# Power.net
KiCad netlist of a schematic drawn in Altium Designer
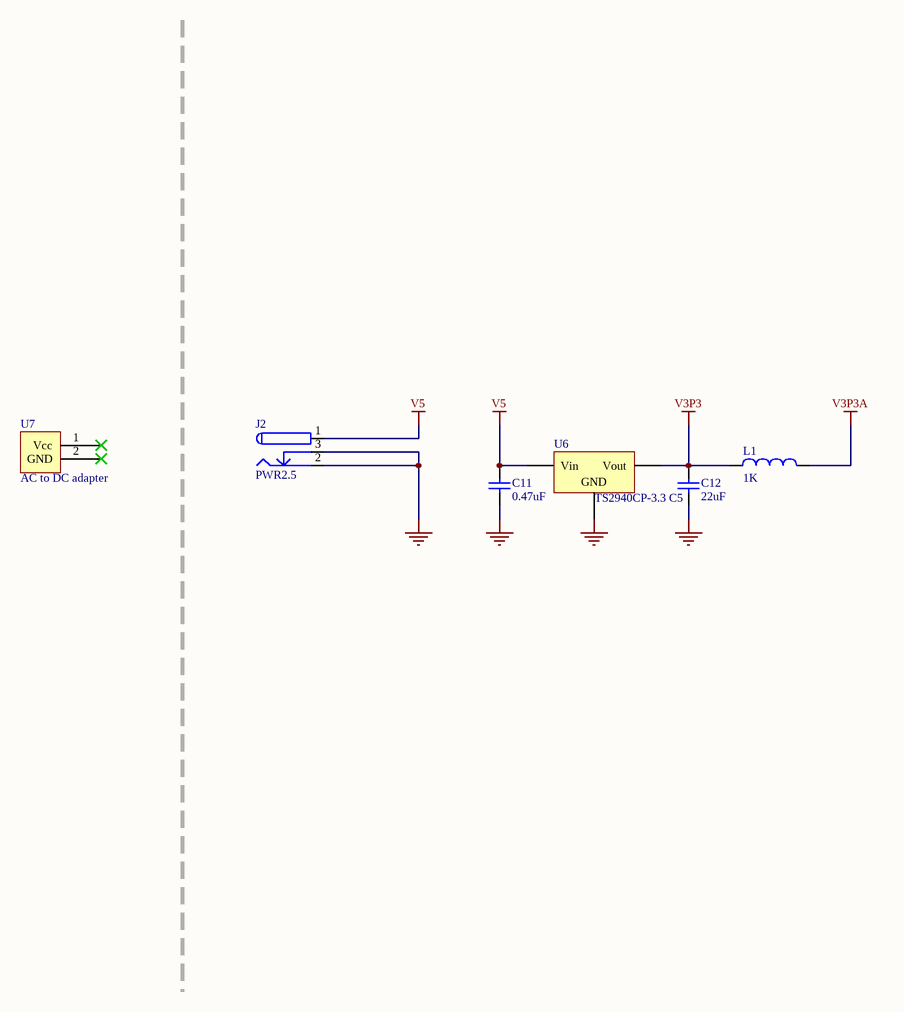
[diagram p0: Power.SchDoc]

(export (version "E")
  (design (tool "Eeschema 10.0.6"))
  (components
    (comp (ref "C11")
      (value "0.47uF")
      (footprint "CAP0603")
      (description "Capacitor")
      (fields (field (name "PUBLISHER") "Altium Limited"))
      (libsource (lib "Miscellaneous Devices") (part "Cap"))
    )
    (comp (ref "C12")
      (value "22uF")
      (footprint "CAP0603")
      (description "Capacitor")
      (fields (field (name "PUBLISHER") "Altium Limited"))
      (libsource (lib "Miscellaneous Devices") (part "Cap"))
    )
    (comp (ref "J2")
      (value "PWR2.5")
      (footprint "MJ-179PH")
      (description "Low Voltage Power Supply Connector")
      (libsource (lib "Miscellaneous Connectors") (part "PWR2.5"))
    )
    (comp (ref "L1")
      (value "1K")
      (footprint "IND0603")
      (description "Inductor")
      (fields (field (name "PUBLISHER") "Altium Limited"))
      (libsource (lib "Miscellaneous Devices") (part "Inductor"))
    )
    (comp (ref "U6")
      (value "TS2940CP-3.3 C5")
      (footprint "TS2940CP-3.3 C5")
      (description "Voltage Regulator")
      (libsource (lib "Miscellaneous Devices") (part "Volt Reg"))
    )
    (comp (ref "U7")
      (value "AC to DC adapter")
      (description "Power adapter")
      (libsource (lib "Components") (part "25HK-AB-050A400-CP"))
    )
  )
  (nets
    (net (code "1") (name "GND") (class "Default")
      (node (ref "C11") (pin "1") (pinfunction "1_1") (pintype "passive"))
      (node (ref "C12") (pin "1") (pinfunction "1_1") (pintype "passive"))
      (node (ref "J2") (pin "2") (pinfunction "2_2") (pintype "power_in"))
      (node (ref "J2") (pin "3") (pinfunction "3_3") (pintype "power_in"))
      (node (ref "U6") (pin "2") (pinfunction "GND_2") (pintype "passive"))
    )
    (net (code "2") (name "V3P3") (class "Default")
      (node (ref "C12") (pin "2") (pinfunction "2_2") (pintype "passive"))
      (node (ref "L1") (pin "1") (pinfunction "1_1") (pintype "passive"))
      (node (ref "U6") (pin "3") (pinfunction "Vout_3") (pintype "passive"))
    )
    (net (code "3") (name "V3P3A") (class "Default")
      (node (ref "L1") (pin "2") (pinfunction "2_2") (pintype "passive"))
    )
    (net (code "4") (name "V5") (class "Default")
      (node (ref "C11") (pin "2") (pinfunction "2_2") (pintype "passive"))
      (node (ref "J2") (pin "1") (pinfunction "1_1") (pintype "power_in"))
      (node (ref "U6") (pin "1") (pinfunction "Vin_1") (pintype "passive"))
    )
    (net (code "5") (name "unconnected-(U7-GND-Pad2)") (class "Default")
      (node (ref "U7") (pin "2") (pinfunction "GND_2") (pintype "power_in+no_connect"))
    )
    (net (code "6") (name "unconnected-(U7-Vcc-Pad1)") (class "Default")
      (node (ref "U7") (pin "1") (pinfunction "Vcc_1") (pintype "power_in+no_connect"))
    )
  )
)
